# Sheet5.net
KiCad netlist of a schematic drawn in Altium Designer
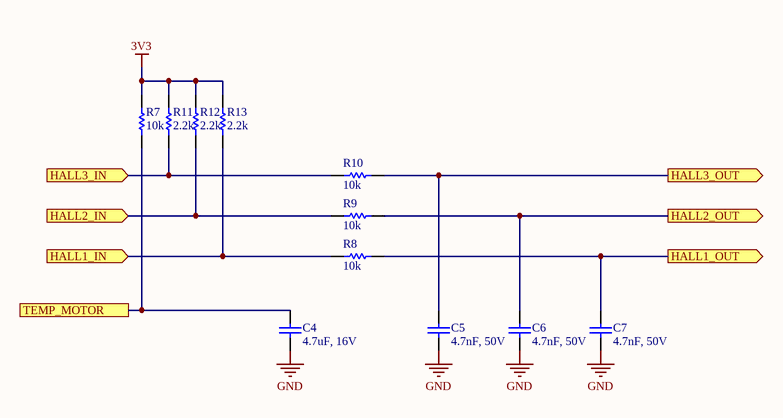
[diagram p0: Sheet5.SchDoc]

(export (version "E")
  (design (tool "Eeschema 10.0.6"))
  (components
    (comp (ref "C4")
      (value "4.7uF, 16V")
      (footprint "SMD-0603 Capacitor")
      (description "CAP 4.7u, 16V, 0603")
      (fields
        (field (name "MANUFACTURER PART NUMBER") "C1608X6S1C475K080AC")
        (field (name "MANUFACTURER") "TDK Corporation")
      )
      (libsource (lib "Master Data Link") (part "CAP"))
    )
    (comp (ref "C5")
      (value "4.7nF, 50V")
      (footprint "SMD-0603 Capacitor")
      (description "CAP 4.7n, 50V, 0603")
      (fields
        (field (name "MANUFACTURER PART NUMBER") "GRM39X472J50D")
        (field (name "MANUFACTURER") "Murata Electronics North America")
      )
      (libsource (lib "Master Data Link") (part "CAP"))
    )
    (comp (ref "C6")
      (value "4.7nF, 50V")
      (footprint "SMD-0603 Capacitor")
      (description "CAP 4.7n, 50V, 0603")
      (fields
        (field (name "MANUFACTURER PART NUMBER") "GRM39X472J50D")
        (field (name "MANUFACTURER") "Murata Electronics North America")
      )
      (libsource (lib "Master Data Link") (part "CAP"))
    )
    (comp (ref "C7")
      (value "4.7nF, 50V")
      (footprint "SMD-0603 Capacitor")
      (description "CAP 4.7n, 50V, 0603")
      (fields
        (field (name "MANUFACTURER PART NUMBER") "GRM39X472J50D")
        (field (name "MANUFACTURER") "Murata Electronics North America")
      )
      (libsource (lib "Master Data Link") (part "CAP"))
    )
    (comp (ref "R7")
      (value "10k")
      (footprint "SMD-0603 Resistor")
      (description "R 10k, 0603")
      (fields
        (field (name "MANUFACTURER PART NUMBER") "RK73H1JTTD1002F")
        (field (name "MANUFACTURER") "KOA Speer")
      )
      (libsource (lib "Master Data Link") (part "RES"))
    )
    (comp (ref "R8")
      (value "10k")
      (footprint "SMD-0603 Resistor")
      (description "R 10k, 0603")
      (fields
        (field (name "MANUFACTURER PART NUMBER") "RK73H1JTTD1002F")
        (field (name "MANUFACTURER") "KOA Speer")
      )
      (libsource (lib "Master Data Link") (part "RES"))
    )
    (comp (ref "R9")
      (value "10k")
      (footprint "SMD-0603 Resistor")
      (description "R 10k, 0603")
      (fields
        (field (name "MANUFACTURER PART NUMBER") "RK73H1JTTD1002F")
        (field (name "MANUFACTURER") "KOA Speer")
      )
      (libsource (lib "Master Data Link") (part "RES"))
    )
    (comp (ref "R10")
      (value "10k")
      (footprint "SMD-0603 Resistor")
      (description "R 10k, 0603")
      (fields
        (field (name "MANUFACTURER PART NUMBER") "RK73H1JTTD1002F")
        (field (name "MANUFACTURER") "KOA Speer")
      )
      (libsource (lib "Master Data Link") (part "RES"))
    )
    (comp (ref "R11")
      (value "2.2k")
      (footprint "SMD-0603 Resistor")
      (description "R 2.2k, 0603")
      (fields
        (field (name "MANUFACTURER PART NUMBER") "RK73H1JTTD2201F")
        (field (name "MANUFACTURER") "KOA Speer")
      )
      (libsource (lib "Master Data Link") (part "RES"))
    )
    (comp (ref "R12")
      (value "2.2k")
      (footprint "SMD-0603 Resistor")
      (description "R 2.2k, 0603")
      (fields
        (field (name "MANUFACTURER PART NUMBER") "RK73H1JTTD2201F")
        (field (name "MANUFACTURER") "KOA Speer")
      )
      (libsource (lib "Master Data Link") (part "RES"))
    )
    (comp (ref "R13")
      (value "2.2k")
      (footprint "SMD-0603 Resistor")
      (description "R 2.2k, 0603")
      (fields
        (field (name "MANUFACTURER PART NUMBER") "RK73H1JTTD2201F")
        (field (name "MANUFACTURER") "KOA Speer")
      )
      (libsource (lib "Master Data Link") (part "RES"))
    )
  )
  (nets
    (net (code "1") (name "/HALL1_IN") (class "Default")
      (node (ref "R13") (pin "1") (pinfunction "1_1") (pintype "passive"))
      (node (ref "R8") (pin "2") (pinfunction "2_2") (pintype "passive"))
    )
    (net (code "2") (name "/HALL1_OUT") (class "Default")
      (node (ref "C7") (pin "2") (pinfunction "2_2") (pintype "passive"))
      (node (ref "R8") (pin "1") (pinfunction "1_1") (pintype "passive"))
    )
    (net (code "3") (name "/HALL2_IN") (class "Default")
      (node (ref "R12") (pin "1") (pinfunction "1_1") (pintype "passive"))
      (node (ref "R9") (pin "2") (pinfunction "2_2") (pintype "passive"))
    )
    (net (code "4") (name "/HALL2_OUT") (class "Default")
      (node (ref "C6") (pin "2") (pinfunction "2_2") (pintype "passive"))
      (node (ref "R9") (pin "1") (pinfunction "1_1") (pintype "passive"))
    )
    (net (code "5") (name "/HALL3_IN") (class "Default")
      (node (ref "R10") (pin "2") (pinfunction "2_2") (pintype "passive"))
      (node (ref "R11") (pin "1") (pinfunction "1_1") (pintype "passive"))
    )
    (net (code "6") (name "/HALL3_OUT") (class "Default")
      (node (ref "C5") (pin "2") (pinfunction "2_2") (pintype "passive"))
      (node (ref "R10") (pin "1") (pinfunction "1_1") (pintype "passive"))
    )
    (net (code "7") (name "/TEMP_MOTOR") (class "Default")
      (node (ref "C4") (pin "2") (pinfunction "2_2") (pintype "passive"))
      (node (ref "R7") (pin "1") (pinfunction "1_1") (pintype "passive"))
    )
    (net (code "8") (name "3V3") (class "Default")
      (node (ref "R11") (pin "2") (pinfunction "2_2") (pintype "passive"))
      (node (ref "R12") (pin "2") (pinfunction "2_2") (pintype "passive"))
      (node (ref "R13") (pin "2") (pinfunction "2_2") (pintype "passive"))
      (node (ref "R7") (pin "2") (pinfunction "2_2") (pintype "passive"))
    )
    (net (code "9") (name "GND") (class "Default")
      (node (ref "C4") (pin "1") (pinfunction "1_1") (pintype "passive"))
      (node (ref "C5") (pin "1") (pinfunction "1_1") (pintype "passive"))
      (node (ref "C6") (pin "1") (pinfunction "1_1") (pintype "passive"))
      (node (ref "C7") (pin "1") (pinfunction "1_1") (pintype "passive"))
    )
  )
)
